# singleNode.net
KiCad netlist of a schematic drawn in EAGLE
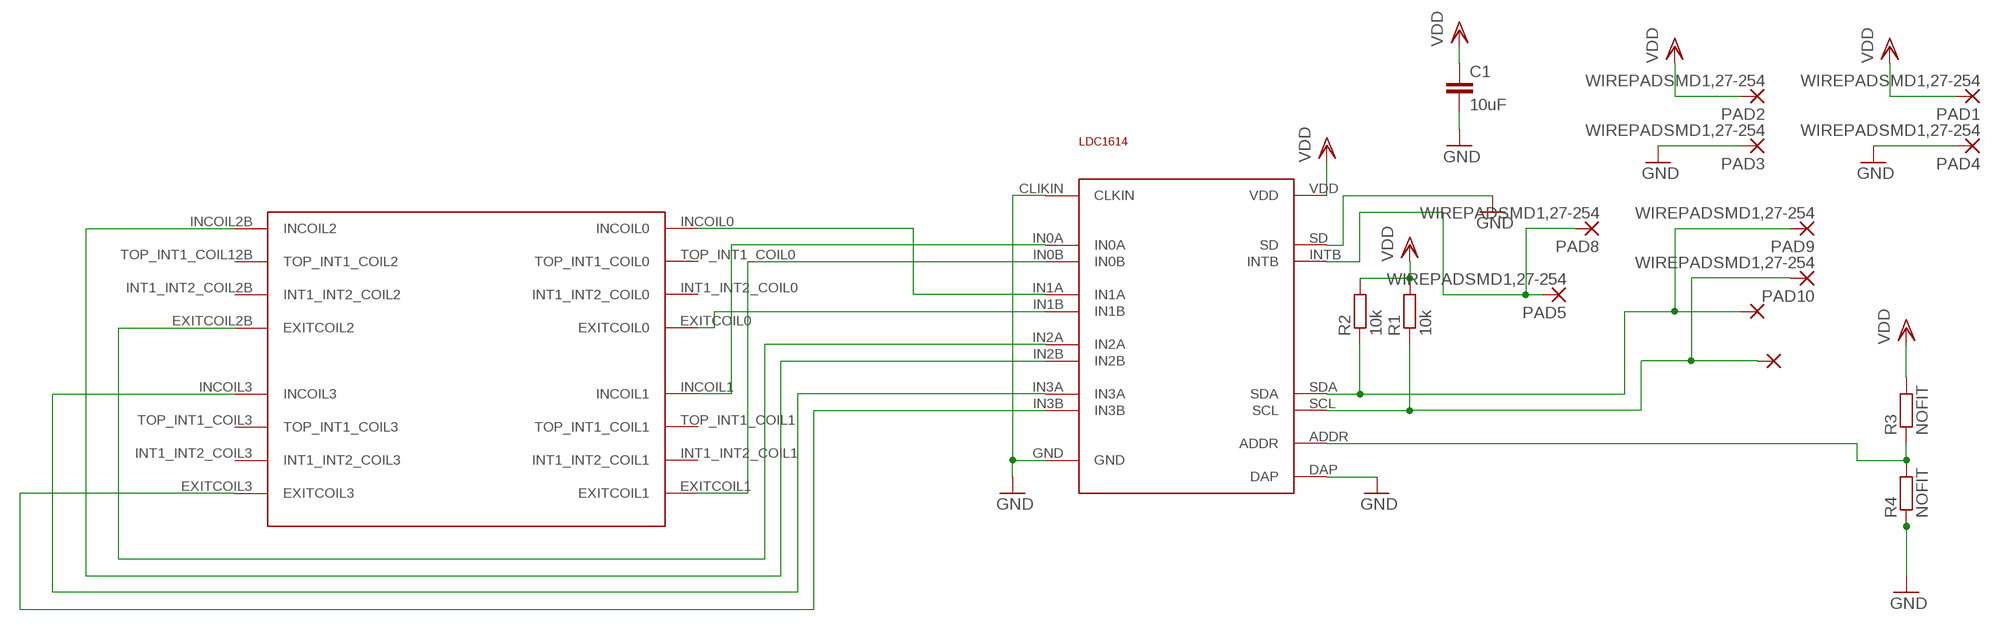
[diagram p0: schematic, sheet 1]

(export (version "E")
  (design (tool "Eeschema 10.0.6"))
  (components
    (comp (ref "C1")
      (value "10uF")
      (footprint "eagle-import:C0402")
      (libsource (lib "eagle-import") (part "C-EUC0402"))
    )
    (comp (ref "PAD1")
      (value "WIREPADSMD1,27-254")
      (footprint "eagle-import:SMD1,27-2,54")
      (libsource (lib "eagle-import") (part "WIREPADSMD1,27-254"))
    )
    (comp (ref "PAD2")
      (value "WIREPADSMD1,27-254")
      (footprint "eagle-import:SMD1,27-2,54")
      (libsource (lib "eagle-import") (part "WIREPADSMD1,27-254"))
    )
    (comp (ref "PAD3")
      (value "WIREPADSMD1,27-254")
      (footprint "eagle-import:SMD1,27-2,54")
      (libsource (lib "eagle-import") (part "WIREPADSMD1,27-254"))
    )
    (comp (ref "PAD4")
      (value "WIREPADSMD1,27-254")
      (footprint "eagle-import:SMD1,27-2,54")
      (libsource (lib "eagle-import") (part "WIREPADSMD1,27-254"))
    )
    (comp (ref "PAD5")
      (value "WIREPADSMD1,27-254")
      (footprint "eagle-import:SMD1,27-2,54")
      (libsource (lib "eagle-import") (part "WIREPADSMD1,27-254"))
    )
    (comp (ref "PAD6")
      (value "WIREPADSMD1,27-254")
      (footprint "eagle-import:SMD1,27-2,54")
      (libsource (lib "eagle-import") (part "WIREPADSMD1,27-254"))
    )
    (comp (ref "PAD7")
      (value "WIREPADSMD1,27-254")
      (footprint "eagle-import:SMD1,27-2,54")
      (libsource (lib "eagle-import") (part "WIREPADSMD1,27-254"))
    )
    (comp (ref "PAD8")
      (value "WIREPADSMD1,27-254")
      (footprint "eagle-import:SMD1,27-2,54")
      (libsource (lib "eagle-import") (part "WIREPADSMD1,27-254"))
    )
    (comp (ref "PAD9")
      (value "WIREPADSMD1,27-254")
      (footprint "eagle-import:SMD1,27-2,54")
      (libsource (lib "eagle-import") (part "WIREPADSMD1,27-254"))
    )
    (comp (ref "PAD10")
      (value "WIREPADSMD1,27-254")
      (footprint "eagle-import:SMD1,27-2,54")
      (libsource (lib "eagle-import") (part "WIREPADSMD1,27-254"))
    )
    (comp (ref "R1")
      (value "10k")
      (footprint "eagle-import:R0402")
      (libsource (lib "eagle-import") (part "R-EU_R0402"))
    )
    (comp (ref "R2")
      (value "10k")
      (footprint "eagle-import:R0402")
      (libsource (lib "eagle-import") (part "R-EU_R0402"))
    )
    (comp (ref "R3")
      (value "NOFIT")
      (footprint "eagle-import:R0201")
      (libsource (lib "eagle-import") (part "R-EU_R0201"))
    )
    (comp (ref "R4")
      (value "NOFIT")
      (footprint "eagle-import:R0201")
      (libsource (lib "eagle-import") (part "R-EU_R0201"))
    )
    (comp (ref "U$2")
      (value "FATFAN_GROUP")
      (footprint "eagle-import:FAT_FAN")
      (libsource (lib "eagle-import") (part "FATFAN_GROUP"))
    )
    (comp (ref "U1")
      (value "LDC1614")
      (footprint "eagle-import:WQFN-16")
      (libsource (lib "eagle-import") (part "LDC1614"))
    )
  )
  (nets
    (net (code "1") (name "GND") (class "Default")
      (node (ref "C1") (pin "2") (pinfunction "2_2") (pintype "passive"))
      (node (ref "PAD3") (pin "1") (pinfunction "P_1") (pintype "passive"))
      (node (ref "PAD4") (pin "1") (pinfunction "P_1") (pintype "passive"))
      (node (ref "R4") (pin "1") (pinfunction "1_1") (pintype "passive"))
      (node (ref "U1") (pin "CLIKIN") (pinfunction "CLKIN_CLIKIN") (pintype "bidirectional"))
      (node (ref "U1") (pin "DAP") (pinfunction "DAP_DAP") (pintype "bidirectional"))
      (node (ref "U1") (pin "GND") (pinfunction "GND_GND") (pintype "bidirectional"))
      (node (ref "U1") (pin "SD") (pinfunction "SD_SD") (pintype "bidirectional"))
    )
    (net (code "2") (name "Net-(PAD5-P)") (class "Default")
      (node (ref "PAD5") (pin "1") (pinfunction "P_1") (pintype "passive"))
      (node (ref "PAD8") (pin "1") (pinfunction "P_1") (pintype "passive"))
      (node (ref "U1") (pin "INTB") (pinfunction "INTB_INTB") (pintype "bidirectional"))
    )
    (net (code "3") (name "Net-(PAD6-P)") (class "Default")
      (node (ref "PAD6") (pin "1") (pinfunction "P_1") (pintype "passive"))
      (node (ref "PAD9") (pin "1") (pinfunction "P_1") (pintype "passive"))
      (node (ref "R2") (pin "1") (pinfunction "1_1") (pintype "passive"))
      (node (ref "U1") (pin "SDA") (pinfunction "SDA_SDA") (pintype "bidirectional"))
    )
    (net (code "4") (name "Net-(PAD10-P)") (class "Default")
      (node (ref "PAD10") (pin "1") (pinfunction "P_1") (pintype "passive"))
      (node (ref "PAD7") (pin "1") (pinfunction "P_1") (pintype "passive"))
      (node (ref "R1") (pin "1") (pinfunction "1_1") (pintype "passive"))
      (node (ref "U1") (pin "SCL") (pinfunction "SCL_SCL") (pintype "bidirectional"))
    )
    (net (code "5") (name "Net-(R3-Pad1)") (class "Default")
      (node (ref "R3") (pin "1") (pinfunction "1_1") (pintype "passive"))
      (node (ref "R4") (pin "2") (pinfunction "2_2") (pintype "passive"))
      (node (ref "U1") (pin "ADDR") (pinfunction "ADDR_ADDR") (pintype "bidirectional"))
    )
    (net (code "6") (name "Net-(U$2-EXITCOIL2)") (class "Default")
      (node (ref "U$2") (pin "EXITCOIL2B") (pinfunction "EXITCOIL2_EXITCOIL2B") (pintype "bidirectional"))
      (node (ref "U1") (pin "IN2A") (pinfunction "IN2A_IN2A") (pintype "bidirectional"))
    )
    (net (code "7") (name "Net-(U$2-INCOIL2)") (class "Default")
      (node (ref "U$2") (pin "INCOIL2B") (pinfunction "INCOIL2_INCOIL2B") (pintype "bidirectional"))
      (node (ref "U1") (pin "IN2B") (pinfunction "IN2B_IN2B") (pintype "bidirectional"))
    )
    (net (code "8") (name "Net-(U$2-PadEXITCOIL0)") (class "Default")
      (node (ref "U$2") (pin "EXITCOIL0") (pinfunction "EXITCOIL0_EXITCOIL0") (pintype "bidirectional"))
      (node (ref "U1") (pin "IN1B") (pinfunction "IN1B_IN1B") (pintype "bidirectional"))
    )
    (net (code "9") (name "Net-(U$2-PadEXITCOIL1)") (class "Default")
      (node (ref "U$2") (pin "EXITCOIL1") (pinfunction "EXITCOIL1_EXITCOIL1") (pintype "bidirectional"))
      (node (ref "U1") (pin "IN0B") (pinfunction "IN0B_IN0B") (pintype "bidirectional"))
    )
    (net (code "10") (name "Net-(U$2-PadEXITCOIL3)") (class "Default")
      (node (ref "U$2") (pin "EXITCOIL3") (pinfunction "EXITCOIL3_EXITCOIL3") (pintype "bidirectional"))
      (node (ref "U1") (pin "IN3B") (pinfunction "IN3B_IN3B") (pintype "bidirectional"))
    )
    (net (code "11") (name "Net-(U$2-PadINCOIL0)") (class "Default")
      (node (ref "U$2") (pin "INCOIL0") (pinfunction "INCOIL0_INCOIL0") (pintype "bidirectional"))
      (node (ref "U1") (pin "IN1A") (pinfunction "IN1A_IN1A") (pintype "bidirectional"))
    )
    (net (code "12") (name "Net-(U$2-PadINCOIL1)") (class "Default")
      (node (ref "U$2") (pin "INCOIL1") (pinfunction "INCOIL1_INCOIL1") (pintype "bidirectional"))
      (node (ref "U1") (pin "IN0A") (pinfunction "IN0A_IN0A") (pintype "bidirectional"))
    )
    (net (code "13") (name "Net-(U$2-PadINCOIL3)") (class "Default")
      (node (ref "U$2") (pin "INCOIL3") (pinfunction "INCOIL3_INCOIL3") (pintype "bidirectional"))
      (node (ref "U1") (pin "IN3A") (pinfunction "IN3A_IN3A") (pintype "bidirectional"))
    )
    (net (code "14") (name "VDD") (class "Default")
      (node (ref "C1") (pin "1") (pinfunction "1_1") (pintype "passive"))
      (node (ref "PAD1") (pin "1") (pinfunction "P_1") (pintype "passive"))
      (node (ref "PAD2") (pin "1") (pinfunction "P_1") (pintype "passive"))
      (node (ref "R1") (pin "2") (pinfunction "2_2") (pintype "passive"))
      (node (ref "R2") (pin "2") (pinfunction "2_2") (pintype "passive"))
      (node (ref "R3") (pin "2") (pinfunction "2_2") (pintype "passive"))
      (node (ref "U1") (pin "VDD") (pinfunction "VDD_VDD") (pintype "bidirectional"))
    )
    (net (code "15") (name "unconnected-(U$2-INT1_INT2_COIL2-PadINT1_INT2_COIL2B)") (class "Default")
      (node (ref "U$2") (pin "INT1_INT2_COIL2B") (pinfunction "INT1_INT2_COIL2_INT1_INT2_COIL2B") (pintype "bidirectional"))
    )
    (net (code "16") (name "unconnected-(U$2-PadINT1_INT2_COIL0)") (class "Default")
      (node (ref "U$2") (pin "INT1_INT2_COIL0") (pinfunction "INT1_INT2_COIL0_INT1_INT2_COIL0") (pintype "bidirectional"))
    )
    (net (code "17") (name "unconnected-(U$2-PadINT1_INT2_COIL1)") (class "Default")
      (node (ref "U$2") (pin "INT1_INT2_COIL1") (pinfunction "INT1_INT2_COIL1_INT1_INT2_COIL1") (pintype "bidirectional"))
    )
    (net (code "18") (name "unconnected-(U$2-PadINT1_INT2_COIL3)") (class "Default")
      (node (ref "U$2") (pin "INT1_INT2_COIL3") (pinfunction "INT1_INT2_COIL3_INT1_INT2_COIL3") (pintype "bidirectional"))
    )
    (net (code "19") (name "unconnected-(U$2-PadTOP_INT1_COIL0)") (class "Default")
      (node (ref "U$2") (pin "TOP_INT1_COIL0") (pinfunction "TOP_INT1_COIL0_TOP_INT1_COIL0") (pintype "bidirectional"))
    )
    (net (code "20") (name "unconnected-(U$2-PadTOP_INT1_COIL1)") (class "Default")
      (node (ref "U$2") (pin "TOP_INT1_COIL1") (pinfunction "TOP_INT1_COIL1_TOP_INT1_COIL1") (pintype "bidirectional"))
    )
    (net (code "21") (name "unconnected-(U$2-PadTOP_INT1_COIL3)") (class "Default")
      (node (ref "U$2") (pin "TOP_INT1_COIL3") (pinfunction "TOP_INT1_COIL3_TOP_INT1_COIL3") (pintype "bidirectional"))
    )
    (net (code "22") (name "unconnected-(U$2-TOP_INT1_COIL2-PadTOP_INT1_COIL12B)") (class "Default")
      (node (ref "U$2") (pin "TOP_INT1_COIL12B") (pinfunction "TOP_INT1_COIL2_TOP_INT1_COIL12B") (pintype "bidirectional"))
    )
  )
)
